# power_unit.net
KiCad netlist of a schematic drawn in Altium Designer
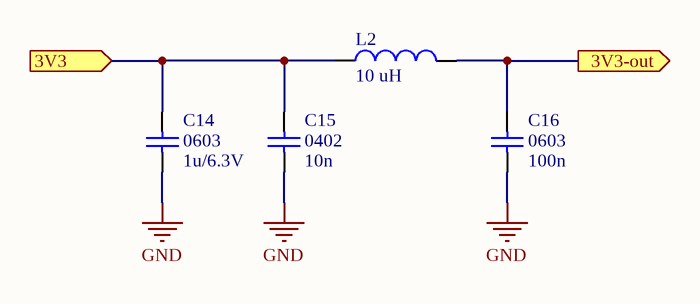
[diagram p0: power_unit.SchDoc]

(export (version "E")
  (design (tool "Eeschema 10.0.6"))
  (components
    (comp (ref "C14")
      (value "0603")
      (footprint "SMD_Capacitor_0603")
      (description "Capacitor")
      (fields (field (name "ALTIUM_VALUE") "1u/6.3V") (field (name "PUBLISHER") "Altium Limited"))
      (libsource (lib "Miscellaneous Devices") (part "Cap"))
    )
    (comp (ref "C15")
      (value "0402")
      (footprint "SMD_Capacitor_0402")
      (description "Capacitor")
      (fields (field (name "ALTIUM_VALUE") "10n") (field (name "PUBLISHER") "Altium Limited"))
      (libsource (lib "Miscellaneous Devices") (part "Cap"))
    )
    (comp (ref "C16")
      (value "0603")
      (footprint "SMD_Capacitor_0603")
      (description "Capacitor")
      (fields (field (name "ALTIUM_VALUE") "100n") (field (name "PUBLISHER") "Altium Limited"))
      (libsource (lib "Miscellaneous Devices") (part "Cap"))
    )
    (comp (ref "L2")
      (value "10 uH")
      (footprint "SMD_Resistor_0603")
      (description "Inductor")
      (fields (field (name "PUBLISHER") "Altium Limited"))
      (libsource (lib "Miscellaneous Devices") (part "Inductor"))
    )
  )
  (nets
    (net (code "1") (name "/3V3") (class "Default")
      (node (ref "C14") (pin "2") (pinfunction "2_2") (pintype "passive"))
      (node (ref "C15") (pin "2") (pinfunction "2_2") (pintype "passive"))
      (node (ref "L2") (pin "1") (pinfunction "1_1") (pintype "passive"))
    )
    (net (code "2") (name "/3V3-out") (class "Default")
      (node (ref "C16") (pin "2") (pinfunction "2_2") (pintype "passive"))
      (node (ref "L2") (pin "2") (pinfunction "2_2") (pintype "passive"))
    )
    (net (code "3") (name "GND") (class "Default")
      (node (ref "C14") (pin "1") (pinfunction "1_1") (pintype "passive"))
      (node (ref "C15") (pin "1") (pinfunction "1_1") (pintype "passive"))
      (node (ref "C16") (pin "1") (pinfunction "1_1") (pintype "passive"))
    )
  )
)
